# VerticalPCBConnection.net
KiCad netlist of a schematic drawn in Altium Designer
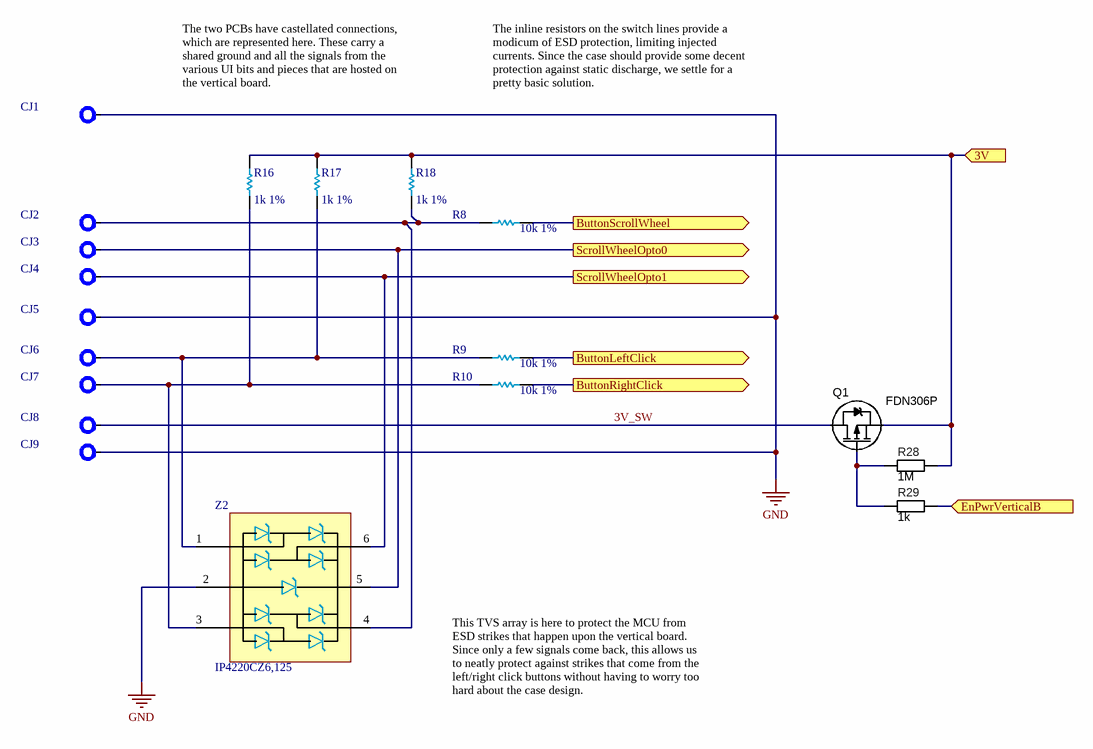
[diagram p0: VerticalPCBConnection.SchDoc]

(export (version "E")
  (design (tool "Eeschema 10.0.6"))
  (components
    (comp (ref "CJ1")
      (value "PCBJointCastellationJoint")
      (footprint "PCBJoint")
      (description "Pad for soldering a castellated PCB edge. Easy way to join two PCBs together.")
      (libsource (lib "PCBFeatures") (part "PCBJoint"))
    )
    (comp (ref "CJ2")
      (value "PCBJointCastellationJoint")
      (footprint "PCBJoint")
      (description "Pad for soldering a castellated PCB edge. Easy way to join two PCBs together.")
      (libsource (lib "PCBFeatures") (part "PCBJoint"))
    )
    (comp (ref "CJ3")
      (value "PCBJointCastellationJoint")
      (footprint "PCBJoint")
      (description "Pad for soldering a castellated PCB edge. Easy way to join two PCBs together.")
      (libsource (lib "PCBFeatures") (part "PCBJoint"))
    )
    (comp (ref "CJ4")
      (value "PCBJointCastellationJoint")
      (footprint "PCBJoint")
      (description "Pad for soldering a castellated PCB edge. Easy way to join two PCBs together.")
      (libsource (lib "PCBFeatures") (part "PCBJoint"))
    )
    (comp (ref "CJ5")
      (value "PCBJointCastellationJoint")
      (footprint "PCBJoint")
      (description "Pad for soldering a castellated PCB edge. Easy way to join two PCBs together.")
      (libsource (lib "PCBFeatures") (part "PCBJoint"))
    )
    (comp (ref "CJ6")
      (value "PCBJointCastellationJoint")
      (footprint "PCBJoint")
      (description "Pad for soldering a castellated PCB edge. Easy way to join two PCBs together.")
      (libsource (lib "PCBFeatures") (part "PCBJoint"))
    )
    (comp (ref "CJ7")
      (value "PCBJointCastellationJoint")
      (footprint "PCBJoint")
      (description "Pad for soldering a castellated PCB edge. Easy way to join two PCBs together.")
      (libsource (lib "PCBFeatures") (part "PCBJoint"))
    )
    (comp (ref "CJ8")
      (value "PCBJointCastellationJoint")
      (footprint "PCBJoint")
      (description "Pad for soldering a castellated PCB edge. Easy way to join two PCBs together.")
      (libsource (lib "PCBFeatures") (part "PCBJoint"))
    )
    (comp (ref "CJ9")
      (value "PCBJointCastellationJoint")
      (footprint "PCBJoint")
      (description "Pad for soldering a castellated PCB edge. Easy way to join two PCBs together.")
      (libsource (lib "PCBFeatures") (part "PCBJoint"))
    )
    (comp (ref "Q1")
      (value "FDN306P")
      (footprint "SMD_SEMI:SOT23-3")
      (description "20 V, P-channel, 90mOhm @ 3V3")
      (libsource (lib "Discrete Semi") (part "MOS_P_PMV75UP"))
    )
    (comp (ref "R8")
      (value "10k 1%")
      (footprint "R0603")
      (description "Chip resistor")
      (fields (field (name "Comment") "0805"))
      (libsource (lib "Chip_Passives") (part "Res 10k 1% 0805"))
    )
    (comp (ref "R9")
      (value "10k 1%")
      (footprint "R0603")
      (description "Chip resistor")
      (fields (field (name "Comment") "0805"))
      (libsource (lib "Chip_Passives") (part "Res 10k 1% 0805"))
    )
    (comp (ref "R10")
      (value "10k 1%")
      (footprint "R0603")
      (description "Chip resistor")
      (fields (field (name "Comment") "0805"))
      (libsource (lib "Chip_Passives") (part "Res 10k 1% 0805"))
    )
    (comp (ref "R16")
      (value "1k 1%")
      (footprint "R0603")
      (description "Chip resistor, 1/8W 100PPM")
      (fields (field (name "Comment") "0805"))
      (libsource (lib "Chip_Passives") (part "Res 1k 1% 0805"))
    )
    (comp (ref "R17")
      (value "1k 1%")
      (footprint "R0603")
      (description "Chip resistor, 1/8W 100PPM")
      (fields (field (name "Comment") "0805"))
      (libsource (lib "Chip_Passives") (part "Res 1k 1% 0805"))
    )
    (comp (ref "R18")
      (value "1k 1%")
      (footprint "R0603")
      (description "Chip resistor, 1/8W 100PPM")
      (fields (field (name "Comment") "0805"))
      (libsource (lib "Chip_Passives") (part "Res 1k 1% 0805"))
    )
    (comp (ref "R28")
      (value "1M")
      (footprint "SMD_PASSIVES:R0603")
      (description "Generic 0603 resistor footprint")
      (libsource (lib "Passives") (part "R0603"))
    )
    (comp (ref "R29")
      (value "1k")
      (footprint "SMD_PASSIVES:R0603")
      (description "Generic 0603 resistor footprint")
      (libsource (lib "Passives") (part "R0603"))
    )
    (comp (ref "Z2")
      (value "IP4220CZ6,125")
      (footprint "PESD3V3S4UD - SOT95P275X110-6N")
      (description "TVS DIODE 5.5V 6TSOP (Low capacitance, USB)")
      (libsource (lib "Diodes") (part "IP4220CZ6,125"))
    )
  )
  (nets
    (net (code "1") (name "/3V") (class "Default")
      (node (ref "Q1") (pin "2") (pinfunction "S_2") (pintype "passive"))
      (node (ref "R16") (pin "2") (pinfunction "2_2") (pintype "passive"))
      (node (ref "R17") (pin "2") (pinfunction "2_2") (pintype "passive"))
      (node (ref "R18") (pin "2") (pinfunction "2_2") (pintype "passive"))
      (node (ref "R28") (pin "2") (pinfunction "2_2") (pintype "passive"))
    )
    (net (code "2") (name "/3V_SW") (class "Default")
      (node (ref "CJ8") (pin "1") (pinfunction "1_1") (pintype "passive"))
      (node (ref "Q1") (pin "3") (pinfunction "D_3") (pintype "passive"))
    )
    (net (code "3") (name "/ButtonLeftClick") (class "Default")
      (node (ref "R9") (pin "2") (pinfunction "2_2") (pintype "passive"))
    )
    (net (code "4") (name "/ButtonRightClick") (class "Default")
      (node (ref "R10") (pin "2") (pinfunction "2_2") (pintype "passive"))
    )
    (net (code "5") (name "/ButtonScrollWheel") (class "Default")
      (node (ref "R8") (pin "2") (pinfunction "2_2") (pintype "passive"))
    )
    (net (code "6") (name "/EnPwrVerticalB") (class "Default")
      (node (ref "R29") (pin "2") (pinfunction "2_2") (pintype "passive"))
    )
    (net (code "7") (name "/ScrollWheelOpto0") (class "Default")
      (node (ref "CJ3") (pin "1") (pinfunction "1_1") (pintype "passive"))
      (node (ref "Z2") (pin "5") (pinfunction "5_5") (pintype "passive"))
    )
    (net (code "8") (name "/ScrollWheelOpto1") (class "Default")
      (node (ref "CJ4") (pin "1") (pinfunction "1_1") (pintype "passive"))
      (node (ref "Z2") (pin "6") (pinfunction "6_6") (pintype "passive"))
    )
    (net (code "9") (name "GND") (class "Default")
      (node (ref "CJ1") (pin "1") (pinfunction "1_1") (pintype "passive"))
      (node (ref "CJ5") (pin "1") (pinfunction "1_1") (pintype "passive"))
      (node (ref "CJ9") (pin "1") (pinfunction "1_1") (pintype "passive"))
      (node (ref "Z2") (pin "2") (pinfunction "2_2") (pintype "passive"))
    )
    (net (code "10") (name "Net-(CJ2-Pad1)") (class "Default")
      (node (ref "CJ2") (pin "1") (pinfunction "1_1") (pintype "passive"))
      (node (ref "R18") (pin "1") (pinfunction "1_1") (pintype "passive"))
      (node (ref "R8") (pin "1") (pinfunction "1_1") (pintype "passive"))
      (node (ref "Z2") (pin "4") (pinfunction "4_4") (pintype "passive"))
    )
    (net (code "11") (name "Net-(CJ6-Pad1)") (class "Default")
      (node (ref "CJ6") (pin "1") (pinfunction "1_1") (pintype "passive"))
      (node (ref "R17") (pin "1") (pinfunction "1_1") (pintype "passive"))
      (node (ref "R9") (pin "1") (pinfunction "1_1") (pintype "passive"))
      (node (ref "Z2") (pin "1") (pinfunction "1_1") (pintype "passive"))
    )
    (net (code "12") (name "Net-(CJ7-Pad1)") (class "Default")
      (node (ref "CJ7") (pin "1") (pinfunction "1_1") (pintype "passive"))
      (node (ref "R10") (pin "1") (pinfunction "1_1") (pintype "passive"))
      (node (ref "R16") (pin "1") (pinfunction "1_1") (pintype "passive"))
      (node (ref "Z2") (pin "3") (pinfunction "3_3") (pintype "passive"))
    )
    (net (code "13") (name "Net-(Q1-G)") (class "Default")
      (node (ref "Q1") (pin "1") (pinfunction "G_1") (pintype "passive"))
      (node (ref "R28") (pin "1") (pinfunction "1_1") (pintype "passive"))
      (node (ref "R29") (pin "1") (pinfunction "1_1") (pintype "passive"))
    )
  )
)
